# Pwr_Brd_3.net
KiCad netlist of a schematic drawn in Altium Designer
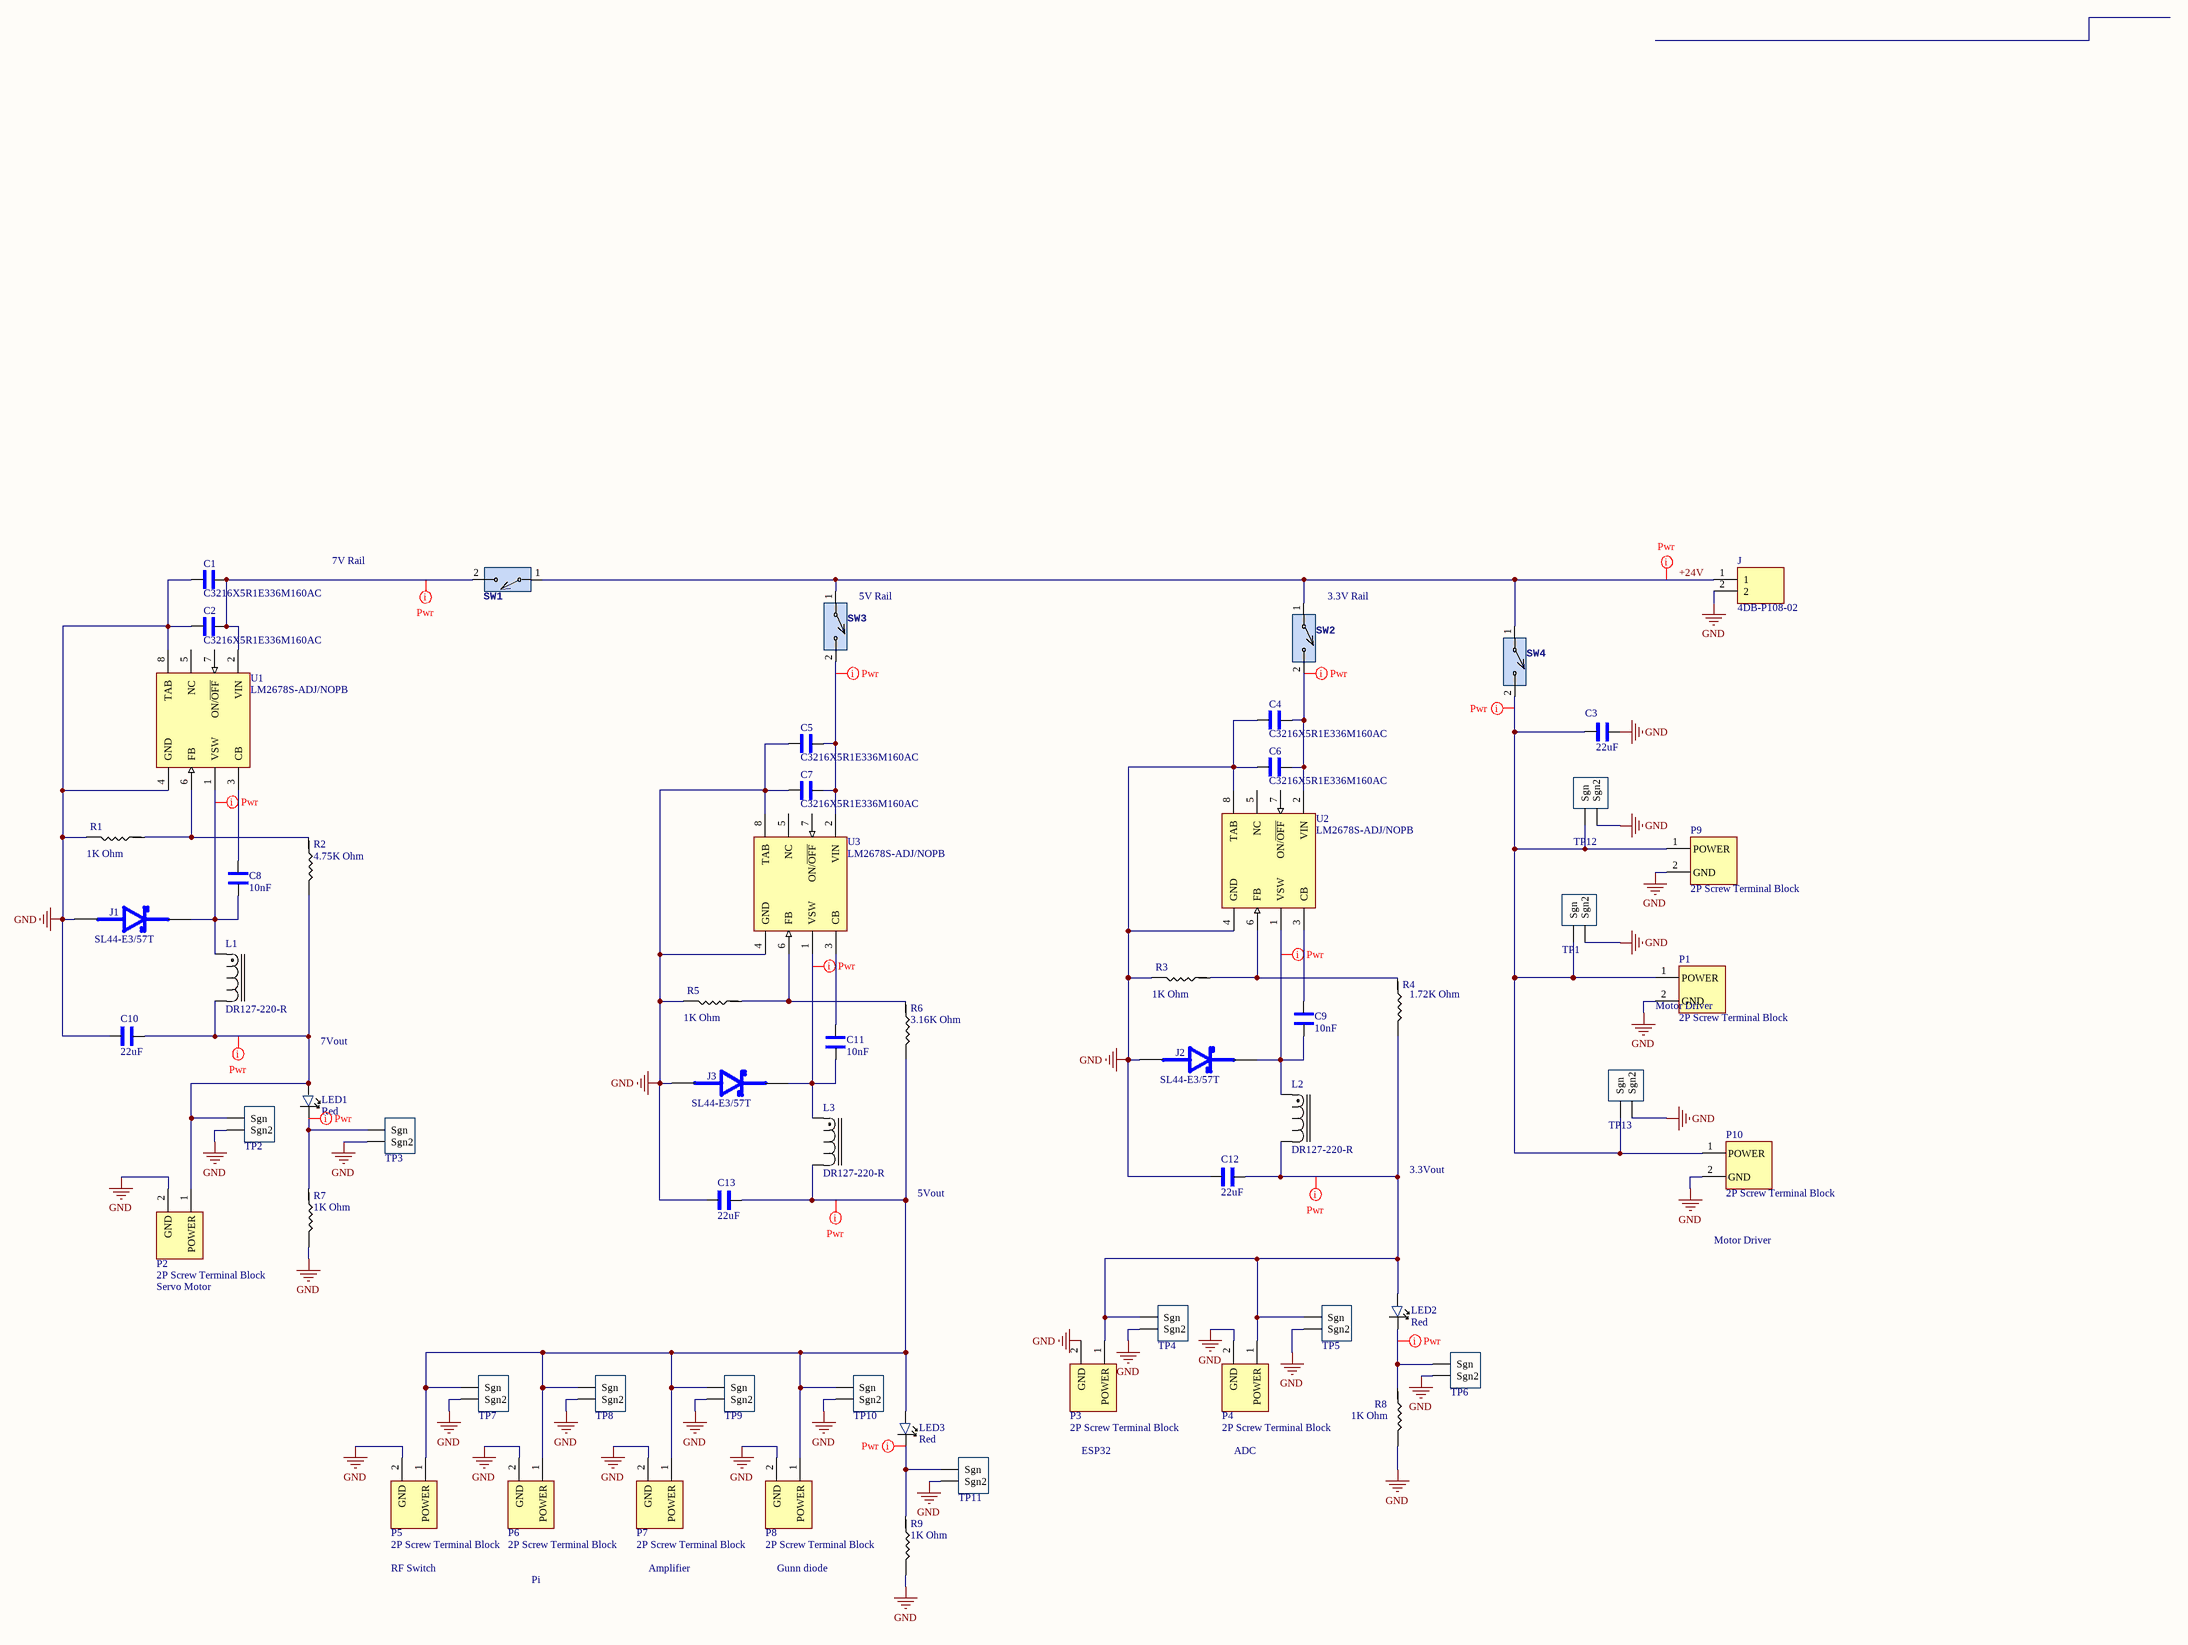
[diagram p0: Pwr_Brd_3.SchDoc]

(export (version "E")
  (design (tool "Eeschema 10.0.6"))
  (components
    (comp (ref "C1")
      (value "C3216X5R1E336M160AC")
      (footprint "CAPC3216X180N")
      (description "Cap Ceramic 33uF 25V X5R 20% Pad SMD 1206 85Â°C Low ESR T/R")
      (fields (field (name "MF") "TDK Electronics"))
      (libsource (lib "C3216X5R1E336M160AC") (part "C3216X5R1E336M160AC"))
    )
    (comp (ref "C2")
      (value "C3216X5R1E336M160AC")
      (footprint "CAPC3216X180N")
      (description "Cap Ceramic 33uF 25V X5R 20% Pad SMD 1206 85Â°C Low ESR T/R")
      (fields (field (name "MF") "TDK Electronics"))
      (libsource (lib "C3216X5R1E336M160AC") (part "C3216X5R1E336M160AC"))
    )
    (comp (ref "C3")
      (value "22uF")
      (footprint "1206_Passive_Capacitor")
      (description "22uF ±10% 25V X5R 1206 Multilayer Ceramic Capacitors MLCC - SMD/SMT RoHS")
      (fields (field (name "MFR PART #") "CL31A226KAHNNNE") (field (name "LCSC PART#") "C12891"))
      (libsource (lib "Capstone_Stock_Library") (part "C_22uF_1206"))
    )
    (comp (ref "C4")
      (value "C3216X5R1E336M160AC")
      (footprint "CAPC3216X180N")
      (description "Cap Ceramic 33uF 25V X5R 20% Pad SMD 1206 85Â°C Low ESR T/R")
      (fields (field (name "MF") "TDK Electronics"))
      (libsource (lib "C3216X5R1E336M160AC") (part "C3216X5R1E336M160AC"))
    )
    (comp (ref "C5")
      (value "C3216X5R1E336M160AC")
      (footprint "CAPC3216X180N")
      (description "Cap Ceramic 33uF 25V X5R 20% Pad SMD 1206 85Â°C Low ESR T/R")
      (fields (field (name "MF") "TDK Electronics"))
      (libsource (lib "C3216X5R1E336M160AC") (part "C3216X5R1E336M160AC"))
    )
    (comp (ref "C6")
      (value "C3216X5R1E336M160AC")
      (footprint "CAPC3216X180N")
      (description "Cap Ceramic 33uF 25V X5R 20% Pad SMD 1206 85Â°C Low ESR T/R")
      (fields (field (name "MF") "TDK Electronics"))
      (libsource (lib "C3216X5R1E336M160AC") (part "C3216X5R1E336M160AC"))
    )
    (comp (ref "C7")
      (value "C3216X5R1E336M160AC")
      (footprint "CAPC3216X180N")
      (description "Cap Ceramic 33uF 25V X5R 20% Pad SMD 1206 85Â°C Low ESR T/R")
      (fields (field (name "MF") "TDK Electronics"))
      (libsource (lib "C3216X5R1E336M160AC") (part "C3216X5R1E336M160AC"))
    )
    (comp (ref "C8")
      (value "10nF")
      (footprint "1206_Passive_Capacitor")
      (description "10nF 50V X7R ±10% 1206 Multilayer Ceramic Capacitors MLCC - SMD/SMT ROHS")
      (fields (field (name "MFR PART #") "CL31B105KBHNNNE") (field (name "LCSC PART#") "C1848"))
      (libsource (lib "Capstone_Stock_Library") (part "C_10nF_1206"))
    )
    (comp (ref "C9")
      (value "10nF")
      (footprint "1206_Passive_Capacitor")
      (description "10nF 50V X7R ±10% 1206 Multilayer Ceramic Capacitors MLCC - SMD/SMT ROHS")
      (fields (field (name "MFR PART #") "CL31B105KBHNNNE") (field (name "LCSC PART#") "C1848"))
      (libsource (lib "Capstone_Stock_Library") (part "C_10nF_1206"))
    )
    (comp (ref "C10")
      (value "22uF")
      (footprint "1206_Passive_Capacitor")
      (description "22uF ±10% 25V X5R 1206 Multilayer Ceramic Capacitors MLCC - SMD/SMT RoHS")
      (fields (field (name "MFR PART #") "CL31A226KAHNNNE") (field (name "LCSC PART#") "C12891"))
      (libsource (lib "Capstone_Stock_Library") (part "C_22uF_1206"))
    )
    (comp (ref "C11")
      (value "10nF")
      (footprint "1206_Passive_Capacitor")
      (description "10nF 50V X7R ±10% 1206 Multilayer Ceramic Capacitors MLCC - SMD/SMT ROHS")
      (fields (field (name "MFR PART #") "CL31B105KBHNNNE") (field (name "LCSC PART#") "C1848"))
      (libsource (lib "Capstone_Stock_Library") (part "C_10nF_1206"))
    )
    (comp (ref "C12")
      (value "22uF")
      (footprint "1206_Passive_Capacitor")
      (description "22uF ±10% 25V X5R 1206 Multilayer Ceramic Capacitors MLCC - SMD/SMT RoHS")
      (fields (field (name "MFR PART #") "CL31A226KAHNNNE") (field (name "LCSC PART#") "C12891"))
      (libsource (lib "Capstone_Stock_Library") (part "C_22uF_1206"))
    )
    (comp (ref "C13")
      (value "22uF")
      (footprint "1206_Passive_Capacitor")
      (description "22uF ±10% 25V X5R 1206 Multilayer Ceramic Capacitors MLCC - SMD/SMT RoHS")
      (fields (field (name "MFR PART #") "CL31A226KAHNNNE") (field (name "LCSC PART#") "C12891"))
      (libsource (lib "Capstone_Stock_Library") (part "C_22uF_1206"))
    )
    (comp (ref "J")
      (value "4DB-P108-02")
      (footprint "TE_2-1437667-4")
      (description "Conn; Term Strip; Barrier; 2Pole; 8.26mmPitch; SnglRow; 22-12; Series 4DB; 20A; 150V")
      (fields (field (name "MF") "TE Connectivity"))
      (libsource (lib "4DB-P108-02") (part "4DB-P108-02"))
    )
    (comp (ref "J1")
      (value "SL44-E3/57T")
      (footprint "DIOM7959X262N")
      (description "Diode Schottky 40 V 4A Surface Mount DO-214AB (SMC)")
      (fields (field (name "MF") "Vishay Semiconductor"))
      (libsource (lib "SL44-E3_57T") (part "SL44-E3/57T"))
    )
    (comp (ref "J2")
      (value "SL44-E3/57T")
      (footprint "DIOM7959X262N")
      (description "Diode Schottky 40 V 4A Surface Mount DO-214AB (SMC)")
      (fields (field (name "MF") "Vishay Semiconductor"))
      (libsource (lib "SL44-E3_57T") (part "SL44-E3/57T"))
    )
    (comp (ref "J3")
      (value "SL44-E3/57T")
      (footprint "DIOM7959X262N")
      (description "Diode Schottky 40 V 4A Surface Mount DO-214AB (SMC)")
      (fields (field (name "MF") "Vishay Semiconductor"))
      (libsource (lib "SL44-E3_57T") (part "SL44-E3/57T"))
    )
    (comp (ref "L1")
      (value "DR127-220-R")
      (footprint "DR127")
      (description "Description")
      (fields (field (name "COPYRIGHT") "Copyright (C) 2025 Ultra Librarian. All rights reserved."))
      (libsource (lib "DR127-220-R") (part "DR127-220-R"))
    )
    (comp (ref "L2")
      (value "DR127-220-R")
      (footprint "DR127")
      (description "Description")
      (fields (field (name "COPYRIGHT") "Copyright (C) 2025 Ultra Librarian. All rights reserved."))
      (libsource (lib "DR127-220-R") (part "DR127-220-R"))
    )
    (comp (ref "L3")
      (value "DR127-220-R")
      (footprint "DR127")
      (description "Description")
      (fields (field (name "COPYRIGHT") "Copyright (C) 2025 Ultra Librarian. All rights reserved."))
      (libsource (lib "DR127-220-R") (part "DR127-220-R"))
    )
    (comp (ref "LED1")
      (value "Red")
      (footprint "LED_1206")
      (description "Red 621~631nm 1206 Light Emitting Diodes (LED) RoHS")
      (fields (field (name "MFR PART #") "15-21/R6C-FQ1R1B/2T") (field (name "LCSC PART#") "C93133"))
      (libsource (lib "Capstone_Stock_Library") (part "LED_RED_1206"))
    )
    (comp (ref "LED2")
      (value "Red")
      (footprint "LED_1206")
      (description "Red 621~631nm 1206 Light Emitting Diodes (LED) RoHS")
      (fields (field (name "MFR PART #") "15-21/R6C-FQ1R1B/2T") (field (name "LCSC PART#") "C93133"))
      (libsource (lib "Capstone_Stock_Library") (part "LED_RED_1206"))
    )
    (comp (ref "LED3")
      (value "Red")
      (footprint "LED_1206")
      (description "Red 621~631nm 1206 Light Emitting Diodes (LED) RoHS")
      (fields (field (name "MFR PART #") "15-21/R6C-FQ1R1B/2T") (field (name "LCSC PART#") "C93133"))
      (libsource (lib "Capstone_Stock_Library") (part "LED_RED_1206"))
    )
    (comp (ref "P1")
      (value "2P Screw Terminal Block")
      (footprint "P_Terminal block 3.5mm-pitch")
      (description "Green Straight pin 3.5mm  pitch; P=3.5mm  Screw terminal ROHS")
      (fields (field (name "MFR PART #") "KF350-3.5-2P") (field (name "MANUFACTURER") "Cixi Kefa Elec"))
      (libsource (lib "Capstone_Stock_Library") (part "P_Terminal block"))
    )
    (comp (ref "P2")
      (value "2P Screw Terminal Block")
      (footprint "P_Terminal block 3.5mm-pitch")
      (description "Green Straight pin 3.5mm  pitch; P=3.5mm  Screw terminal ROHS")
      (fields (field (name "MFR PART #") "KF350-3.5-2P") (field (name "MANUFACTURER") "Cixi Kefa Elec"))
      (libsource (lib "") (part "P_Terminal block_1"))
    )
    (comp (ref "P3")
      (value "2P Screw Terminal Block")
      (footprint "P_Terminal block 3.5mm-pitch")
      (description "Green Straight pin 3.5mm  pitch; P=3.5mm  Screw terminal ROHS")
      (fields (field (name "MFR PART #") "KF350-3.5-2P") (field (name "MANUFACTURER") "Cixi Kefa Elec"))
      (libsource (lib "") (part "P_Terminal block_1"))
    )
    (comp (ref "P4")
      (value "2P Screw Terminal Block")
      (footprint "P_Terminal block 3.5mm-pitch")
      (description "Green Straight pin 3.5mm  pitch; P=3.5mm  Screw terminal ROHS")
      (fields (field (name "MFR PART #") "KF350-3.5-2P") (field (name "MANUFACTURER") "Cixi Kefa Elec"))
      (libsource (lib "") (part "P_Terminal block_1"))
    )
    (comp (ref "P5")
      (value "2P Screw Terminal Block")
      (footprint "P_Terminal block 3.5mm-pitch")
      (description "Green Straight pin 3.5mm  pitch; P=3.5mm  Screw terminal ROHS")
      (fields (field (name "MFR PART #") "KF350-3.5-2P") (field (name "MANUFACTURER") "Cixi Kefa Elec"))
      (libsource (lib "") (part "P_Terminal block_1"))
    )
    (comp (ref "P6")
      (value "2P Screw Terminal Block")
      (footprint "P_Terminal block 3.5mm-pitch")
      (description "Green Straight pin 3.5mm  pitch; P=3.5mm  Screw terminal ROHS")
      (fields (field (name "MFR PART #") "KF350-3.5-2P") (field (name "MANUFACTURER") "Cixi Kefa Elec"))
      (libsource (lib "") (part "P_Terminal block_1"))
    )
    (comp (ref "P7")
      (value "2P Screw Terminal Block")
      (footprint "P_Terminal block 3.5mm-pitch")
      (description "Green Straight pin 3.5mm  pitch; P=3.5mm  Screw terminal ROHS")
      (fields (field (name "MFR PART #") "KF350-3.5-2P") (field (name "MANUFACTURER") "Cixi Kefa Elec"))
      (libsource (lib "") (part "P_Terminal block_1"))
    )
    (comp (ref "P8")
      (value "2P Screw Terminal Block")
      (footprint "P_Terminal block 3.5mm-pitch")
      (description "Green Straight pin 3.5mm  pitch; P=3.5mm  Screw terminal ROHS")
      (fields (field (name "MFR PART #") "KF350-3.5-2P") (field (name "MANUFACTURER") "Cixi Kefa Elec"))
      (libsource (lib "") (part "P_Terminal block_1"))
    )
    (comp (ref "P9")
      (value "2P Screw Terminal Block")
      (footprint "P_Terminal block 3.5mm-pitch")
      (description "Green Straight pin 3.5mm  pitch; P=3.5mm  Screw terminal ROHS")
      (fields (field (name "MFR PART #") "KF350-3.5-2P") (field (name "MANUFACTURER") "Cixi Kefa Elec"))
      (libsource (lib "Capstone_Stock_Library") (part "P_Terminal block"))
    )
    (comp (ref "P10")
      (value "2P Screw Terminal Block")
      (footprint "P_Terminal block 3.5mm-pitch")
      (description "Green Straight pin 3.5mm  pitch; P=3.5mm  Screw terminal ROHS")
      (fields (field (name "MFR PART #") "KF350-3.5-2P") (field (name "MANUFACTURER") "Cixi Kefa Elec"))
      (libsource (lib "Capstone_Stock_Library") (part "P_Terminal block"))
    )
    (comp (ref "R1")
      (value "1K Ohm")
      (footprint "1206_Passive_Resitor")
      (description "CHIP RESISTOR - SURFACE MOUNT 1KOHMS ±1% 1/4W 1206 ROHS")
      (fields (field (name "MFR PART #") "RNCP1206FTD1K00CT") (field (name "LCSC PART#") "C4410"))
      (libsource (lib "Capstone_Stock_Library") (part "R_1K_1206"))
    )
    (comp (ref "R2")
      (value "4.75K Ohm")
      (footprint "1206_Passive_Resitor")
      (description "CHIP RESISTOR - SURFACE MOUNT 1KOHMS ±1% 1/4W 1206 ROHS")
      (fields (field (name "MFR PART #") "RNCP1206FTD1K00CT") (field (name "LCSC PART#") "C4410"))
      (libsource (lib "Capstone_Stock_Library") (part "R_1K_1206"))
    )
    (comp (ref "R3")
      (value "1K Ohm")
      (footprint "1206_Passive_Resitor")
      (description "CHIP RESISTOR - SURFACE MOUNT 1KOHMS ±1% 1/4W 1206 ROHS")
      (fields (field (name "MFR PART #") "RNCP1206FTD1K00CT") (field (name "LCSC PART#") "C4410"))
      (libsource (lib "Capstone_Stock_Library") (part "R_1K_1206"))
    )
    (comp (ref "R4")
      (value "1.72K Ohm")
      (footprint "1206_Passive_Resitor")
      (description "CHIP RESISTOR - SURFACE MOUNT 1KOHMS ±1% 1/4W 1206 ROHS")
      (fields (field (name "MFR PART #") "RNCP1206FTD1K00CT") (field (name "LCSC PART#") "C4410"))
      (libsource (lib "Capstone_Stock_Library") (part "R_1K_1206"))
    )
    (comp (ref "R5")
      (value "1K Ohm")
      (footprint "1206_Passive_Resitor")
      (description "CHIP RESISTOR - SURFACE MOUNT 1KOHMS ±1% 1/4W 1206 ROHS")
      (fields (field (name "MFR PART #") "RNCP1206FTD1K00CT") (field (name "LCSC PART#") "C4410"))
      (libsource (lib "Capstone_Stock_Library") (part "R_1K_1206"))
    )
    (comp (ref "R6")
      (value "3.16K Ohm")
      (footprint "1206_Passive_Resitor")
      (description "CHIP RESISTOR - SURFACE MOUNT 1KOHMS ±1% 1/4W 1206 ROHS")
      (fields (field (name "MFR PART #") "RNCP1206FTD1K00CT") (field (name "LCSC PART#") "C4410"))
      (libsource (lib "Capstone_Stock_Library") (part "R_1K_1206"))
    )
    (comp (ref "R7")
      (value "1K Ohm")
      (footprint "1206_Passive_Resitor")
      (description "CHIP RESISTOR - SURFACE MOUNT 1KOHMS ±1% 1/4W 1206 ROHS")
      (fields (field (name "MFR PART #") "RNCP1206FTD1K00CT") (field (name "LCSC PART#") "C4410"))
      (libsource (lib "Capstone_Stock_Library") (part "R_1K_1206"))
    )
    (comp (ref "R8")
      (value "1K Ohm")
      (footprint "1206_Passive_Resitor")
      (description "CHIP RESISTOR - SURFACE MOUNT 1KOHMS ±1% 1/4W 1206 ROHS")
      (fields (field (name "MFR PART #") "RNCP1206FTD1K00CT") (field (name "LCSC PART#") "C4410"))
      (libsource (lib "Capstone_Stock_Library") (part "R_1K_1206"))
    )
    (comp (ref "R9")
      (value "1K Ohm")
      (footprint "1206_Passive_Resitor")
      (description "CHIP RESISTOR - SURFACE MOUNT 1KOHMS ±1% 1/4W 1206 ROHS")
      (fields (field (name "MFR PART #") "RNCP1206FTD1K00CT") (field (name "LCSC PART#") "C4410"))
      (libsource (lib "Capstone_Stock_Library") (part "R_1K_1206"))
    )
    (comp (ref "SW1")
      (value "SW_2Pin_100mil_Switch")
      (footprint "2Pin-Header-Conn")
      (description "2Pin Header")
      (fields (field (name "LCSC PART#") "C124375"))
      (libsource (lib "") (part "SW_2Pin_100mil_Switch_1"))
    )
    (comp (ref "SW2")
      (value "SW_2Pin_100mil_Switch")
      (footprint "2Pin-Header-Conn")
      (description "2Pin Header")
      (fields (field (name "LCSC PART#") "C124375"))
      (libsource (lib "Capstone_Stock_Library") (part "SW_2Pin_100mil_Switch"))
    )
    (comp (ref "SW3")
      (value "SW_2Pin_100mil_Switch")
      (footprint "2Pin-Header-Conn")
      (description "2Pin Header")
      (fields (field (name "LCSC PART#") "C124375"))
      (libsource (lib "Capstone_Stock_Library") (part "SW_2Pin_100mil_Switch"))
    )
    (comp (ref "SW4")
      (value "SW_2Pin_100mil_Switch")
      (footprint "2Pin-Header-Conn")
      (description "2Pin Header")
      (fields (field (name "LCSC PART#") "C124375"))
      (libsource (lib "Capstone_Stock_Library") (part "SW_2Pin_100mil_Switch"))
    )
    (comp (ref "TP1")
      (value "10x Probe TP")
      (footprint "TP_Diff_Probe")
      (description "Test Point 300 mil centers")
      (libsource (lib "") (part "TP_Diff_Probe_1"))
    )
    (comp (ref "TP2")
      (value "10x Probe TP")
      (footprint "TP_Diff_Probe")
      (description "Test Point 300 mil centers")
      (libsource (lib "Capstone_Stock_Library") (part "TP_Diff_Probe"))
    )
    (comp (ref "TP3")
      (value "10x Probe TP")
      (footprint "TP_Diff_Probe")
      (description "Test Point 300 mil centers")
      (libsource (lib "Capstone_Stock_Library") (part "TP_Diff_Probe"))
    )
    (comp (ref "TP4")
      (value "10x Probe TP")
      (footprint "TP_Diff_Probe")
      (description "Test Point 300 mil centers")
      (libsource (lib "Capstone_Stock_Library") (part "TP_Diff_Probe"))
    )
    (comp (ref "TP5")
      (value "10x Probe TP")
      (footprint "TP_Diff_Probe")
      (description "Test Point 300 mil centers")
      (libsource (lib "Capstone_Stock_Library") (part "TP_Diff_Probe"))
    )
    (comp (ref "TP6")
      (value "10x Probe TP")
      (footprint "TP_Diff_Probe")
      (description "Test Point 300 mil centers")
      (libsource (lib "Capstone_Stock_Library") (part "TP_Diff_Probe"))
    )
    (comp (ref "TP7")
      (value "10x Probe TP")
      (footprint "TP_Diff_Probe")
      (description "Test Point 300 mil centers")
      (libsource (lib "Capstone_Stock_Library") (part "TP_Diff_Probe"))
    )
    (comp (ref "TP8")
      (value "10x Probe TP")
      (footprint "TP_Diff_Probe")
      (description "Test Point 300 mil centers")
      (libsource (lib "Capstone_Stock_Library") (part "TP_Diff_Probe"))
    )
    (comp (ref "TP9")
      (value "10x Probe TP")
      (footprint "TP_Diff_Probe")
      (description "Test Point 300 mil centers")
      (libsource (lib "Capstone_Stock_Library") (part "TP_Diff_Probe"))
    )
    (comp (ref "TP10")
      (value "10x Probe TP")
      (footprint "TP_Diff_Probe")
      (description "Test Point 300 mil centers")
      (libsource (lib "Capstone_Stock_Library") (part "TP_Diff_Probe"))
    )
    (comp (ref "TP11")
      (value "10x Probe TP")
      (footprint "TP_Diff_Probe")
      (description "Test Point 300 mil centers")
      (libsource (lib "Capstone_Stock_Library") (part "TP_Diff_Probe"))
    )
    (comp (ref "TP12")
      (value "10x Probe TP")
      (footprint "TP_Diff_Probe")
      (description "Test Point 300 mil centers")
      (libsource (lib "") (part "TP_Diff_Probe_1"))
    )
    (comp (ref "TP13")
      (value "10x Probe TP")
      (footprint "TP_Diff_Probe")
      (description "Test Point 300 mil centers")
      (libsource (lib "") (part "TP_Diff_Probe_1"))
    )
    (comp (ref "U1")
      (value "LM2678S-ADJ/NOPB")
      (footprint "KTW0007B_N")
      (description "SIMPLE SWITCHER® High Efficiency 5A Step-Down Voltage Regulator, 7-pin TO-263, Pb-Free")
      (fields (field (name "MANUFACTURER") "Texas Instruments"))
      (libsource (lib "Altium Content Vault") (part "PM-REG-LM2678S"))
    )
    (comp (ref "U2")
      (value "LM2678S-ADJ/NOPB")
      (footprint "KTW0007B_N")
      (description "SIMPLE SWITCHER® High Efficiency 5A Step-Down Voltage Regulator, 7-pin TO-263, Pb-Free")
      (fields (field (name "MANUFACTURER") "Texas Instruments"))
      (libsource (lib "Altium Content Vault") (part "PM-REG-LM2678S"))
    )
    (comp (ref "U3")
      (value "LM2678S-ADJ/NOPB")
      (footprint "KTW0007B_N")
      (description "SIMPLE SWITCHER® High Efficiency 5A Step-Down Voltage Regulator, 7-pin TO-263, Pb-Free")
      (fields (field (name "MANUFACTURER") "Texas Instruments"))
      (libsource (lib "Altium Content Vault") (part "PM-REG-LM2678S"))
    )
  )
  (nets
    (net (code "1") (name "/+24V") (class "Default")
      (node (ref "J") (pin "1") (pinfunction "1_1") (pintype "passive"))
      (node (ref "SW1") (pin "1") (pinfunction "1_1") (pintype "passive"))
      (node (ref "SW2") (pin "1") (pinfunction "1_1") (pintype "passive"))
      (node (ref "SW3") (pin "1") (pinfunction "1_1") (pintype "passive"))
      (node (ref "SW4") (pin "1") (pinfunction "1_1") (pintype "passive"))
    )
    (net (code "2") (name "GND") (class "Default")
      (node (ref "C1") (pin "1") (pinfunction "1_1") (pintype "passive"))
      (node (ref "C10") (pin "1") (pinfunction "1_1") (pintype "passive"))
      (node (ref "C12") (pin "1") (pinfunction "1_1") (pintype "passive"))
      (node (ref "C13") (pin "1") (pinfunction "1_1") (pintype "passive"))
      (node (ref "C2") (pin "1") (pinfunction "1_1") (pintype "passive"))
      (node (ref "C3") (pin "2") (pinfunction "2_2") (pintype "passive"))
      (node (ref "C4") (pin "1") (pinfunction "1_1") (pintype "passive"))
      (node (ref "C5") (pin "1") (pinfunction "1_1") (pintype "passive"))
      (node (ref "C6") (pin "1") (pinfunction "1_1") (pintype "passive"))
      (node (ref "C7") (pin "1") (pinfunction "1_1") (pintype "passive"))
      (node (ref "J") (pin "2") (pinfunction "2_2") (pintype "passive"))
      (node (ref "J1") (pin "A") (pinfunction "A_A") (pintype "passive"))
      (node (ref "J2") (pin "A") (pinfunction "A_A") (pintype "passive"))
      (node (ref "J3") (pin "A") (pinfunction "A_A") (pintype "passive"))
      (node (ref "P1") (pin "2") (pinfunction "GND_2") (pintype "passive"))
      (node (ref "P10") (pin "2") (pinfunction "GND_2") (pintype "passive"))
      (node (ref "P2") (pin "2") (pinfunction "GND_2") (pintype "passive"))
      (node (ref "P3") (pin "2") (pinfunction "GND_2") (pintype "passive"))
      (node (ref "P4") (pin "2") (pinfunction "GND_2") (pintype "passive"))
      (node (ref "P5") (pin "2") (pinfunction "GND_2") (pintype "passive"))
      (node (ref "P6") (pin "2") (pinfunction "GND_2") (pintype "passive"))
      (node (ref "P7") (pin "2") (pinfunction "GND_2") (pintype "passive"))
      (node (ref "P8") (pin "2") (pinfunction "GND_2") (pintype "passive"))
      (node (ref "P9") (pin "2") (pinfunction "GND_2") (pintype "passive"))
      (node (ref "R1") (pin "2") (pinfunction "2_2") (pintype "passive"))
      (node (ref "R3") (pin "2") (pinfunction "2_2") (pintype "passive"))
      (node (ref "R5") (pin "2") (pinfunction "2_2") (pintype "passive"))
      (node (ref "R7") (pin "2") (pinfunction "2_2") (pintype "passive"))
      (node (ref "R8") (pin "2") (pinfunction "2_2") (pintype "passive"))
      (node (ref "R9") (pin "2") (pinfunction "2_2") (pintype "passive"))
      (node (ref "TP1") (pin "2") (pinfunction "Sgn2_2") (pintype "passive"))
      (node (ref "TP10") (pin "2") (pinfunction "Sgn2_2") (pintype "passive"))
      (node (ref "TP11") (pin "2") (pinfunction "Sgn2_2") (pintype "passive"))
      (node (ref "TP12") (pin "2") (pinfunction "Sgn2_2") (pintype "passive"))
      (node (ref "TP13") (pin "2") (pinfunction "Sgn2_2") (pintype "passive"))
      (node (ref "TP2") (pin "2") (pinfunction "Sgn2_2") (pintype "passive"))
      (node (ref "TP3") (pin "2") (pinfunction "Sgn2_2") (pintype "passive"))
      (node (ref "TP4") (pin "2") (pinfunction "Sgn2_2") (pintype "passive"))
      (node (ref "TP5") (pin "2") (pinfunction "Sgn2_2") (pintype "passive"))
      (node (ref "TP6") (pin "2") (pinfunction "Sgn2_2") (pintype "passive"))
      (node (ref "TP7") (pin "2") (pinfunction "Sgn2_2") (pintype "passive"))
      (node (ref "TP8") (pin "2") (pinfunction "Sgn2_2") (pintype "passive"))
      (node (ref "TP9") (pin "2") (pinfunction "Sgn2_2") (pintype "passive"))
      (node (ref "U1") (pin "4") (pinfunction "GND_4") (pintype "power_in"))
      (node (ref "U1") (pin "8") (pinfunction "TAB_8") (pintype "power_in"))
      (node (ref "U2") (pin "4") (pinfunction "GND_4") (pintype "power_in"))
      (node (ref "U2") (pin "8") (pinfunction "TAB_8") (pintype "power_in"))
      (node (ref "U3") (pin "4") (pinfunction "GND_4") (pintype "power_in"))
      (node (ref "U3") (pin "8") (pinfunction "TAB_8") (pintype "power_in"))
    )
    (net (code "3") (name "Net-(P1-POWER)") (class "Default")
      (node (ref "C3") (pin "1") (pinfunction "1_1") (pintype "passive"))
      (node (ref "P1") (pin "1") (pinfunction "POWER_1") (pintype "passive"))
      (node (ref "P10") (pin "1") (pinfunction "POWER_1") (pintype "passive"))
      (node (ref "P9") (pin "1") (pinfunction "POWER_1") (pintype "passive"))
      (node (ref "SW4") (pin "2") (pinfunction "2_2") (pintype "passive"))
      (node (ref "TP1") (pin "1") (pinfunction "Sgn_1") (pintype "passive"))
      (node (ref "TP12") (pin "1") (pinfunction "Sgn_1") (pintype "passive"))
      (node (ref "TP13") (pin "1") (pinfunction "Sgn_1") (pintype "passive"))
    )
    (net (code "4") (name "Net-(P2-POWER)") (class "Default")
      (node (ref "C10") (pin "2") (pinfunction "2_2") (pintype "passive"))
      (node (ref "L1") (pin "2") (pinfunction "2_2") (pintype "passive"))
      (node (ref "LED1") (pin "1") (pinfunction "1_1") (pintype "passive"))
      (node (ref "P2") (pin "1") (pinfunction "POWER_1") (pintype "passive"))
      (node (ref "R2") (pin "2") (pinfunction "2_2") (pintype "passive"))
      (node (ref "TP2") (pin "1") (pinfunction "Sgn_1") (pintype "passive"))
    )
    (net (code "5") (name "Net-(P3-POWER)") (class "Default")
      (node (ref "C12") (pin "2") (pinfunction "2_2") (pintype "passive"))
      (node (ref "L2") (pin "2") (pinfunction "2_2") (pintype "passive"))
      (node (ref "LED2") (pin "1") (pinfunction "1_1") (pintype "passive"))
      (node (ref "P3") (pin "1") (pinfunction "POWER_1") (pintype "passive"))
      (node (ref "P4") (pin "1") (pinfunction "POWER_1") (pintype "passive"))
      (node (ref "R4") (pin "2") (pinfunction "2_2") (pintype "passive"))
      (node (ref "TP4") (pin "1") (pinfunction "Sgn_1") (pintype "passive"))
      (node (ref "TP5") (pin "1") (pinfunction "Sgn_1") (pintype "passive"))
    )
    (net (code "6") (name "Net-(P5-POWER)") (class "Default")
      (node (ref "C13") (pin "2") (pinfunction "2_2") (pintype "passive"))
      (node (ref "L3") (pin "2") (pinfunction "2_2") (pintype "passive"))
      (node (ref "LED3") (pin "1") (pinfunction "1_1") (pintype "passive"))
      (node (ref "P5") (pin "1") (pinfunction "POWER_1") (pintype "passive"))
      (node (ref "P6") (pin "1") (pinfunction "POWER_1") (pintype "passive"))
      (node (ref "P7") (pin "1") (pinfunction "POWER_1") (pintype "passive"))
      (node (ref "P8") (pin "1") (pinfunction "POWER_1") (pintype "passive"))
      (node (ref "R6") (pin "2") (pinfunction "2_2") (pintype "passive"))
      (node (ref "TP10") (pin "1") (pinfunction "Sgn_1") (pintype "passive"))
      (node (ref "TP7") (pin "1") (pinfunction "Sgn_1") (pintype "passive"))
      (node (ref "TP8") (pin "1") (pinfunction "Sgn_1") (pintype "passive"))
      (node (ref "TP9") (pin "1") (pinfunction "Sgn_1") (pintype "passive"))
    )
    (net (code "7") (name "Net-(TP3-Sgn)") (class "Default")
      (node (ref "LED1") (pin "2") (pinfunction "2_2") (pintype "passive"))
      (node (ref "R7") (pin "1") (pinfunction "1_1") (pintype "passive"))
      (node (ref "TP3") (pin "1") (pinfunction "Sgn_1") (pintype "passive"))
    )
    (net (code "8") (name "Net-(TP6-Sgn)") (class "Default")
      (node (ref "LED2") (pin "2") (pinfunction "2_2") (pintype "passive"))
      (node (ref "R8") (pin "1") (pinfunction "1_1") (pintype "passive"))
      (node (ref "TP6") (pin "1") (pinfunction "Sgn_1") (pintype "passive"))
    )
    (net (code "9") (name "Net-(TP11-Sgn)") (class "Default")
      (node (ref "LED3") (pin "2") (pinfunction "2_2") (pintype "passive"))
      (node (ref "R9") (pin "1") (pinfunction "1_1") (pintype "passive"))
      (node (ref "TP11") (pin "1") (pinfunction "Sgn_1") (pintype "passive"))
    )
    (net (code "10") (name "Net-(U1-CB)") (class "Default")
      (node (ref "C8") (pin "2") (pinfunction "2_2") (pintype "passive"))
      (node (ref "U1") (pin "3") (pinfunction "CB_3") (pintype "passive"))
    )
    (net (code "11") (name "Net-(U1-FB)") (class "Default")
      (node (ref "R1") (pin "1") (pinfunction "1_1") (pintype "passive"))
      (node (ref "R2") (pin "1") (pinfunction "1_1") (pintype "passive"))
      (node (ref "U1") (pin "6") (pinfunction "FB_6") (pintype "input"))
    )
    (net (code "12") (name "Net-(U1-VIN)") (class "Default")
      (node (ref "C1") (pin "2") (pinfunction "2_2") (pintype "passive"))
      (node (ref "C2") (pin "2") (pinfunction "2_2") (pintype "passive"))
      (node (ref "SW1") (pin "2") (pinfunction "2_2") (pintype "passive"))
      (node (ref "U1") (pin "2") (pinfunction "VIN_2") (pintype "power_in"))
    )
    (net (code "13") (name "Net-(U1-VSW)") (class "Default")
      (node (ref "C8") (pin "1") (pinfunction "1_1") (pintype "passive"))
      (node (ref "J1") (pin "C") (pinfunction "C_C") (pintype "passive"))
      (node (ref "L1") (pin "1") (pinfunction "1_1") (pintype "passive"))
      (node (ref "U1") (pin "1") (pinfunction "VSW_1") (pintype "power_in"))
    )
    (net (code "14") (name "Net-(U2-CB)") (class "Default")
      (node (ref "C9") (pin "2") (pinfunction "2_2") (pintype "passive"))
      (node (ref "U2") (pin "3") (pinfunction "CB_3") (pintype "passive"))
    )
    (net (code "15") (name "Net-(U2-FB)") (class "Default")
      (node (ref "R3") (pin "1") (pinfunction "1_1") (pintype "passive"))
      (node (ref "R4") (pin "1") (pinfunction "1_1") (pintype "passive"))
      (node (ref "U2") (pin "6") (pinfunction "FB_6") (pintype "input"))
    )
    (net (code "16") (name "Net-(U2-VIN)") (class "Default")
      (node (ref "C4") (pin "2") (pinfunction "2_2") (pintype "passive"))
      (node (ref "C6") (pin "2") (pinfunction "2_2") (pintype "passive"))
      (node (ref "SW2") (pin "2") (pinfunction "2_2") (pintype "passive"))
      (node (ref "U2") (pin "2") (pinfunction "VIN_2") (pintype "power_in"))
    )
    (net (code "17") (name "Net-(U2-VSW)") (class "Default")
      (node (ref "C9") (pin "1") (pinfunction "1_1") (pintype "passive"))
      (node (ref "J2") (pin "C") (pinfunction "C_C") (pintype "passive"))
      (node (ref "L2") (pin "1") (pinfunction "1_1") (pintype "passive"))
      (node (ref "U2") (pin "1") (pinfunction "VSW_1") (pintype "power_in"))
    )
    (net (code "18") (name "Net-(U3-CB)") (class "Default")
      (node (ref "C11") (pin "2") (pinfunction "2_2") (pintype "passive"))
      (node (ref "U3") (pin "3") (pinfunction "CB_3") (pintype "passive"))
    )
    (net (code "19") (name "Net-(U3-FB)") (class "Default")
      (node (ref "R5") (pin "1") (pinfunction "1_1") (pintype "passive"))
      (node (ref "R6") (pin "1") (pinfunction "1_1") (pintype "passive"))
      (node (ref "U3") (pin "6") (pinfunction "FB_6") (pintype "input"))
    )
    (net (code "20") (name "Net-(U3-VIN)") (class "Default")
      (node (ref "C5") (pin "2") (pinfunction "2_2") (pintype "passive"))
      (node (ref "C7") (pin "2") (pinfunction "2_2") (pintype "passive"))
      (node (ref "SW3") (pin "2") (pinfunction "2_2") (pintype "passive"))
      (node (ref "U3") (pin "2") (pinfunction "VIN_2") (pintype "power_in"))
    )
    (net (code "21") (name "Net-(U3-VSW)") (class "Default")
      (node (ref "C11") (pin "1") (pinfunction "1_1") (pintype "passive"))
      (node (ref "J3") (pin "C") (pinfunction "C_C") (pintype "passive"))
      (node (ref "L3") (pin "1") (pinfunction "1_1") (pintype "passive"))
      (node (ref "U3") (pin "1") (pinfunction "VSW_1") (pintype "power_in"))
    )
    (net (code "22") (name "unconnected-(U1-NC-Pad5)") (class "Default")
      (node (ref "U1") (pin "5") (pinfunction "NC_5") (pintype "passive"))
    )
    (net (code "23") (name "unconnected-(U1-ON{slash}~{OFF}-Pad7)") (class "Default")
      (node (ref "U1") (pin "7") (pinfunction "ON/~{OFF}_7") (pintype "input"))
    )
    (net (code "24") (name "unconnected-(U2-NC-Pad5)") (class "Default")
      (node (ref "U2") (pin "5") (pinfunction "NC_5") (pintype "passive"))
    )
    (net (code "25") (name "unconnected-(U2-ON{slash}~{OFF}-Pad7)") (class "Default")
      (node (ref "U2") (pin "7") (pinfunction "ON/~{OFF}_7") (pintype "input"))
    )
    (net (code "26") (name "unconnected-(U3-NC-Pad5)") (class "Default")
      (node (ref "U3") (pin "5") (pinfunction "NC_5") (pintype "passive"))
    )
    (net (code "27") (name "unconnected-(U3-ON{slash}~{OFF}-Pad7)") (class "Default")
      (node (ref "U3") (pin "7") (pinfunction "ON/~{OFF}_7") (pintype "input"))
    )
  )
)
